# RGB_led_breakout.net
KiCad netlist of a schematic drawn in EAGLE
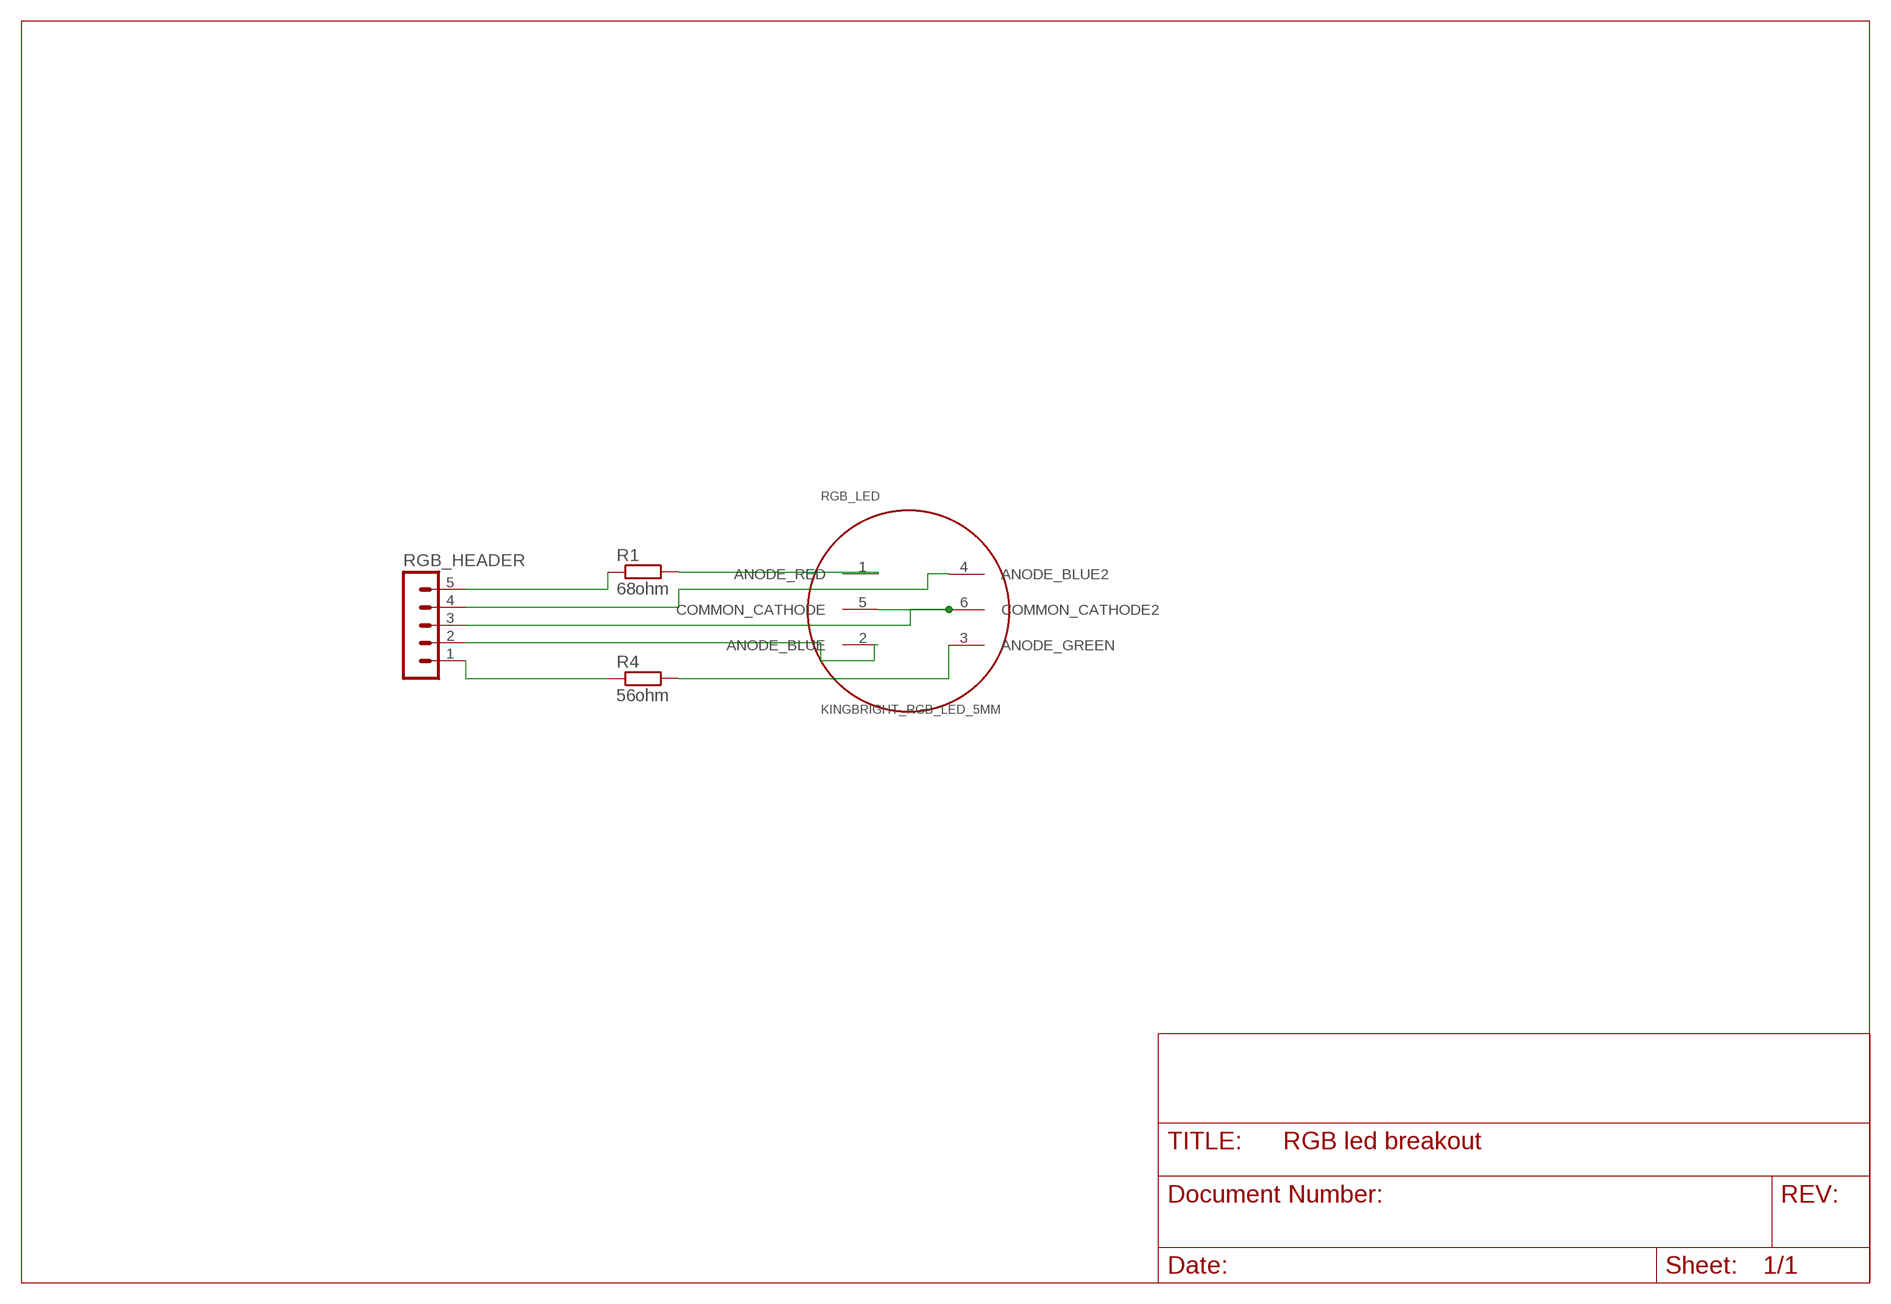
[diagram p0: schematic, sheet 1]

(export (version "E")
  (design (tool "Eeschema 10.0.6"))
  (components
    (comp (ref "R1")
      (value "68ohm")
      (footprint "eagle-import:0207_7")
      (libsource (lib "eagle-import") (part "R-EU_0207/7"))
    )
    (comp (ref "R4")
      (value "56ohm")
      (footprint "eagle-import:0207_7")
      (libsource (lib "eagle-import") (part "R-EU_0207/7"))
    )
    (comp (ref "RGB_HEADER")
      (value "MA05-1")
      (footprint "eagle-import:MA05-1")
      (libsource (lib "eagle-import") (part "MA05-1"))
    )
    (comp (ref "RGB_LED")
      (value "KINGBRIGHT_RGB_LED_5MM")
      (footprint "eagle-import:LF5WAEMBGMBW")
      (libsource (lib "eagle-import") (part "KINGBRIGHT_RGB_LED_5MM"))
    )
  )
  (nets
    (net (code "1") (name "Net-(R1-Pad1)") (class "Default")
      (node (ref "R1") (pin "1") (pinfunction "1_1") (pintype "passive"))
      (node (ref "RGB_HEADER") (pin "5") (pinfunction "5_5") (pintype "passive"))
    )
    (net (code "2") (name "Net-(R4-Pad1)") (class "Default")
      (node (ref "R4") (pin "1") (pinfunction "1_1") (pintype "passive"))
      (node (ref "RGB_HEADER") (pin "1") (pinfunction "1_1") (pintype "passive"))
    )
    (net (code "3") (name "Net-(RGB_LED-ANODE_BLUE)") (class "Default")
      (node (ref "RGB_HEADER") (pin "2") (pinfunction "2_2") (pintype "passive"))
      (node (ref "RGB_LED") (pin "2") (pinfunction "ANODE_BLUE_2") (pintype "bidirectional"))
    )
    (net (code "4") (name "Net-(RGB_LED-ANODE_BLUE2)") (class "Default")
      (node (ref "RGB_HEADER") (pin "4") (pinfunction "4_4") (pintype "passive"))
      (node (ref "RGB_LED") (pin "4") (pinfunction "ANODE_BLUE2_4") (pintype "bidirectional"))
    )
    (net (code "5") (name "Net-(RGB_LED-ANODE_GREEN)") (class "Default")
      (node (ref "R4") (pin "2") (pinfunction "2_2") (pintype "passive"))
      (node (ref "RGB_LED") (pin "3") (pinfunction "ANODE_GREEN_3") (pintype "bidirectional"))
    )
    (net (code "6") (name "Net-(RGB_LED-ANODE_RED)") (class "Default")
      (node (ref "R1") (pin "2") (pinfunction "2_2") (pintype "passive"))
      (node (ref "RGB_LED") (pin "1") (pinfunction "ANODE_RED_1") (pintype "bidirectional"))
    )
    (net (code "7") (name "Net-(RGB_LED-COMMON_CATHODE)") (class "Default")
      (node (ref "RGB_HEADER") (pin "3") (pinfunction "3_3") (pintype "passive"))
      (node (ref "RGB_LED") (pin "5") (pinfunction "COMMON_CATHODE_5") (pintype "power_in"))
      (node (ref "RGB_LED") (pin "6") (pinfunction "COMMON_CATHODE2_6") (pintype "power_in"))
    )
  )
)
